# UVandLight_I2C_V1.net
KiCad netlist of a schematic drawn in EAGLE
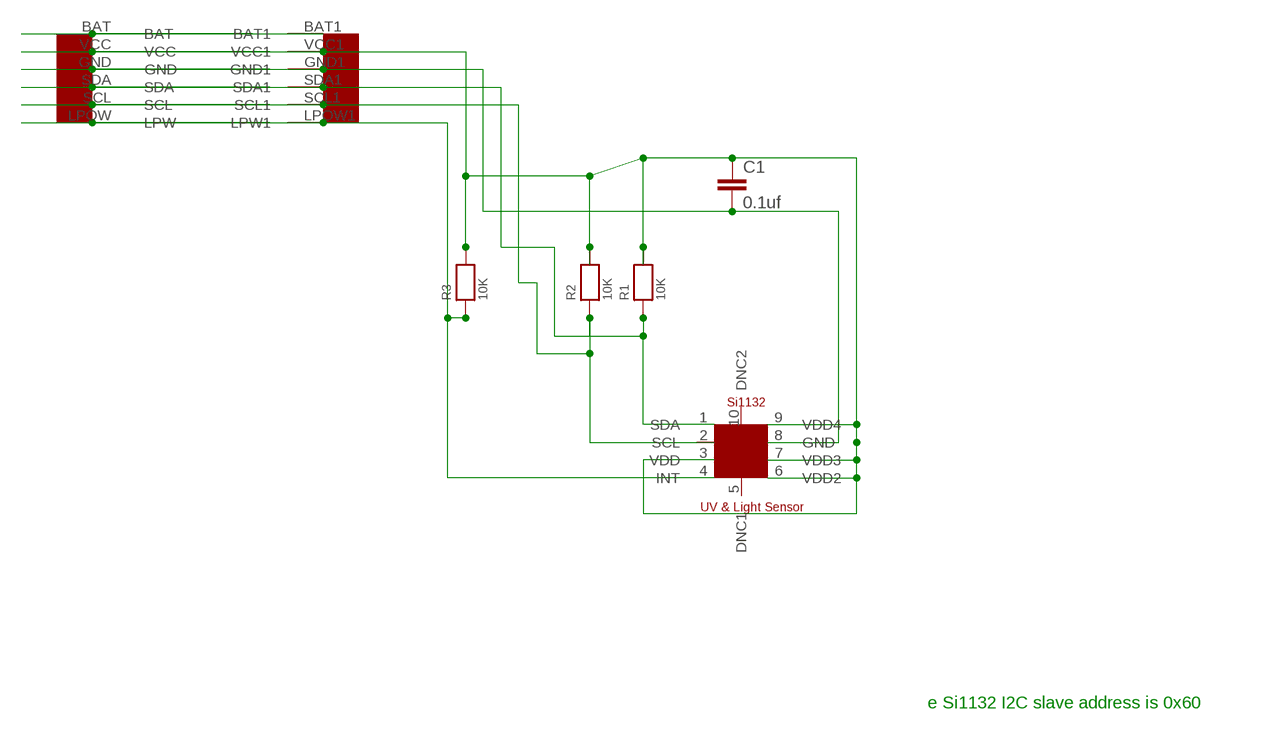
[diagram p0: schematic, sheet 1]

(export (version "E")
  (design (tool "Eeschema 10.0.6"))
  (components
    (comp (ref "C1")
      (value "0.1uf")
      (footprint "eagle-import:0402-CAP")
      (libsource (lib "eagle-import") (part "CAP0402-CAP"))
    )
    (comp (ref "R1")
      (value "10K")
      (footprint "eagle-import:0402")
      (libsource (lib "eagle-import") (part "RESISTOR0402"))
    )
    (comp (ref "R2")
      (value "10K")
      (footprint "eagle-import:0402")
      (libsource (lib "eagle-import") (part "RESISTOR0402"))
    )
    (comp (ref "R3")
      (value "10K")
      (footprint "eagle-import:0402")
      (libsource (lib "eagle-import") (part "RESISTOR0402"))
    )
    (comp (ref "U$1")
      (value "EASYI2C6PINHEADER")
      (footprint "eagle-import:EASYI2C6PINHEADER")
      (libsource (lib "eagle-import") (part "EASYI2C6PINHEADER"))
    )
    (comp (ref "U$2")
      (value "UV-SI1132")
      (footprint "eagle-import:UV-SI1132")
      (libsource (lib "eagle-import") (part "UV-SI1132"))
    )
  )
  (nets
    (net (code "1") (name "Net-(U$1-LPW)") (class "Default")
      (node (ref "R3") (pin "1") (pinfunction "1_1") (pintype "passive"))
      (node (ref "U$1") (pin "LPOW") (pinfunction "LPW_LPOW") (pintype "bidirectional"))
      (node (ref "U$1") (pin "LPOW1") (pinfunction "LPW1_LPOW1") (pintype "bidirectional"))
      (node (ref "U$2") (pin "4") (pinfunction "INT_4") (pintype "bidirectional"))
    )
    (net (code "2") (name "Net-(U$1-PadBAT)") (class "Default")
      (node (ref "U$1") (pin "BAT") (pinfunction "BAT_BAT") (pintype "bidirectional"))
      (node (ref "U$1") (pin "BAT1") (pinfunction "BAT1_BAT1") (pintype "bidirectional"))
    )
    (net (code "3") (name "Net-(U$2-GND)") (class "Default")
      (node (ref "C1") (pin "2") (pinfunction "2_2") (pintype "passive"))
      (node (ref "U$1") (pin "GND") (pinfunction "GND_GND") (pintype "bidirectional"))
      (node (ref "U$1") (pin "GND1") (pinfunction "GND1_GND1") (pintype "bidirectional"))
      (node (ref "U$2") (pin "8") (pinfunction "GND_8") (pintype "bidirectional"))
    )
    (net (code "4") (name "Net-(U$2-SCL)") (class "Default")
      (node (ref "R2") (pin "1") (pinfunction "1_1") (pintype "passive"))
      (node (ref "U$1") (pin "SCL") (pinfunction "SCL_SCL") (pintype "bidirectional"))
      (node (ref "U$1") (pin "SCL1") (pinfunction "SCL1_SCL1") (pintype "bidirectional"))
      (node (ref "U$2") (pin "2") (pinfunction "SCL_2") (pintype "bidirectional"))
    )
    (net (code "5") (name "Net-(U$2-SDA)") (class "Default")
      (node (ref "R1") (pin "1") (pinfunction "1_1") (pintype "passive"))
      (node (ref "U$1") (pin "SDA") (pinfunction "SDA_SDA") (pintype "bidirectional"))
      (node (ref "U$1") (pin "SDA1") (pinfunction "SDA1_SDA1") (pintype "bidirectional"))
      (node (ref "U$2") (pin "1") (pinfunction "SDA_1") (pintype "bidirectional"))
    )
    (net (code "6") (name "Net-(U$2-VDD)") (class "Default")
      (node (ref "C1") (pin "1") (pinfunction "1_1") (pintype "passive"))
      (node (ref "R1") (pin "2") (pinfunction "2_2") (pintype "passive"))
      (node (ref "R2") (pin "2") (pinfunction "2_2") (pintype "passive"))
      (node (ref "R3") (pin "2") (pinfunction "2_2") (pintype "passive"))
      (node (ref "U$1") (pin "VCC") (pinfunction "VCC_VCC") (pintype "bidirectional"))
      (node (ref "U$1") (pin "VCC1") (pinfunction "VCC1_VCC1") (pintype "bidirectional"))
      (node (ref "U$2") (pin "3") (pinfunction "VDD_3") (pintype "bidirectional"))
      (node (ref "U$2") (pin "6") (pinfunction "VDD2_6") (pintype "bidirectional"))
      (node (ref "U$2") (pin "7") (pinfunction "VDD3_7") (pintype "bidirectional"))
      (node (ref "U$2") (pin "9") (pinfunction "VDD4_9") (pintype "bidirectional"))
    )
    (net (code "7") (name "unconnected-(U$2-DNC1-Pad5)") (class "Default")
      (node (ref "U$2") (pin "5") (pinfunction "DNC1_5") (pintype "bidirectional"))
    )
    (net (code "8") (name "unconnected-(U$2-DNC2-Pad10)") (class "Default")
      (node (ref "U$2") (pin "10") (pinfunction "DNC2_10") (pintype "bidirectional"))
    )
  )
)
